# SALIDA_RF.net
KiCad netlist of a schematic drawn in Altium Designer
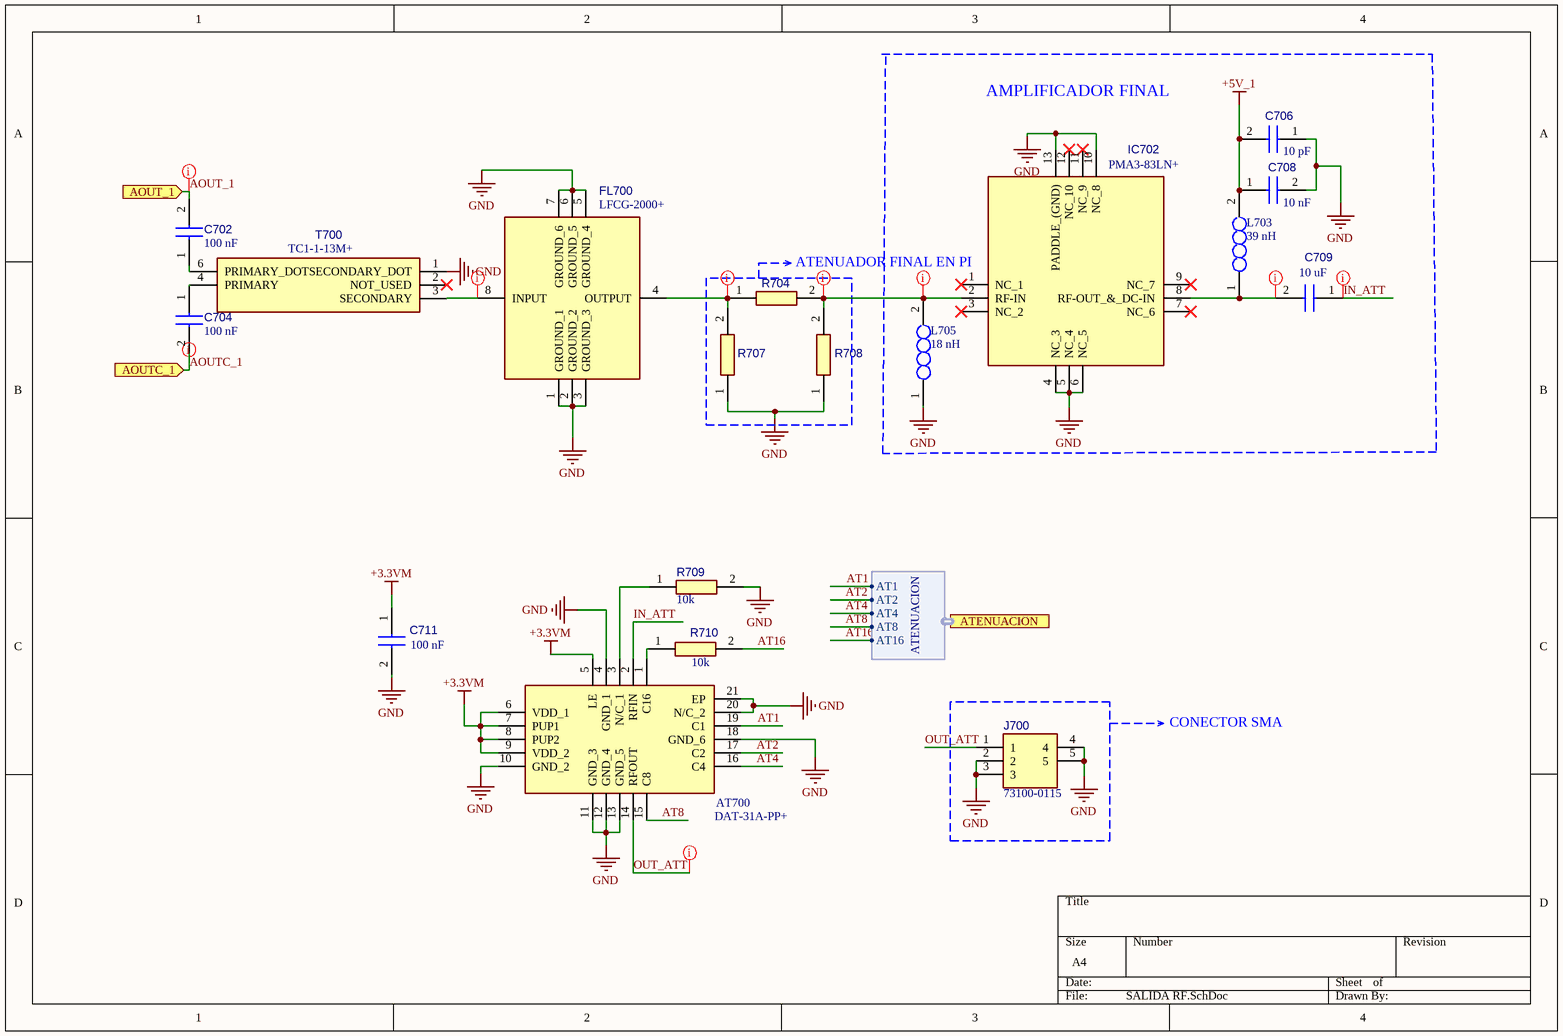
[diagram p0: SALIDA RF.SchDoc]

(export (version "E")
  (design (tool "Eeschema 10.0.6"))
  (components
    (comp (ref "AT700")
      (value "DAT-31A-PP+")
      (footprint "SamacSys:QFN50P400X400X85-21N")
      (description "Attenuator or Isolator")
      (fields (field (name "MOUSER PART NUMBER") "139-DAT-31A-PP+"))
      (libsource (lib "SamacSys") (part "DAT-31A-PP+"))
    )
    (comp (ref "C702")
      (value "100 nF")
      (footprint "SamacSys:C0603")
      (description "Capacitor")
      (fields (field (name "MANUFACTURER_PART_NUMBER") "C0603H470J5GACTU"))
      (libsource (lib "*") (part "C0603H470J5GACTU"))
    )
    (comp (ref "C704")
      (value "100 nF")
      (footprint "SamacSys:C0603")
      (description "Capacitor")
      (fields (field (name "MANUFACTURER_PART_NUMBER") "C0603H470J5GACTU"))
      (libsource (lib "*") (part "C0603H470J5GACTU"))
    )
    (comp (ref "C706")
      (value "10 pF")
      (footprint "SamacSys:C0603")
      (description "Capacitor")
      (fields (field (name "MANUFACTURER_PART_NUMBER") "C0603H470J5GACTU"))
      (libsource (lib "*") (part "C0603H470J5GACTU"))
    )
    (comp (ref "C708")
      (value "10 nF")
      (footprint "SamacSys:C0603")
      (description "Capacitor")
      (fields (field (name "MANUFACTURER_PART_NUMBER") "C0603H470J5GACTU"))
      (libsource (lib "*") (part "C0603H470J5GACTU"))
    )
    (comp (ref "C709")
      (value "10 uF")
      (footprint "SamacSys:C0603")
      (description "Capacitor")
      (fields (field (name "MANUFACTURER_PART_NUMBER") "C0603H470J5GACTU"))
      (libsource (lib "*") (part "C0603H470J5GACTU"))
    )
    (comp (ref "C711")
      (value "100 nF")
      (footprint "SamacSys:C0603")
      (description "Capacitor")
      (fields (field (name "MANUFACTURER_PART_NUMBER") "C0603H470J5GACTU"))
      (libsource (lib "*") (part "C0603H470J5GACTU"))
    )
    (comp (ref "FL700")
      (value "LFCG-2000+")
      (footprint "SamacSys:LFCG2000")
      (description "Filter")
      (fields (field (name "MOUSER PART NUMBER") "139-LFCG-2000+"))
      (libsource (lib "*") (part "LFCG-2000+"))
    )
    (comp (ref "IC702")
      (value "PMA3-83LN+")
      (footprint "SamacSys:QFN51P300X300X89-13N")
      (description "Integrated Circuit")
      (fields (field (name "MOUSER PART NUMBER") "139-PMA3-83LN"))
      (libsource (lib "*") (part "PMA3-83LN+"))
    )
    (comp (ref "J700")
      (value "73100-0115")
      (footprint "SamacSys:731000115")
      (description "Connector")
      (fields (field (name "MOUSER PART NUMBER") "538-73100-0115"))
      (libsource (lib "*") (part "73100-0115"))
    )
    (comp (ref "L703")
      (value "39 nH")
      (footprint "SamacSys:INDC1608X95N")
      (description "Inductor")
      (fields
        (field (name "MANUFACTURER_PART_NUMBER") "AIML-0603-100K-T")
        (field (name "MOUSER PART NUMBER") "815-AIML-0603-100KT")
      )
      (libsource (lib "*") (part "AIML-0603-100K-T"))
    )
    (comp (ref "L705")
      (value "18 nH")
      (footprint "SamacSys:INDC1608X95N")
      (description "Inductor")
      (fields
        (field (name "MANUFACTURER_PART_NUMBER") "AIML-0603-100K-T")
        (field (name "MOUSER PART NUMBER") "815-AIML-0603-100KT")
      )
      (libsource (lib "*") (part "AIML-0603-100K-T"))
    )
    (comp (ref "R704")
      (value "0")
      (footprint "SamacSys:RESC1608X55N")
      (description "Resistor")
      (fields
        (field (name "MANUFACTURER_PART_NUMBER") "CR0603-FX-1431ELF")
        (field (name "MOUSER PART NUMBER") "652-CR0603FX-1431ELF")
      )
      (libsource (lib "*") (part "CR0603-FX-1431ELF"))
    )
    (comp (ref "R707")
      (value "ATENUADOR")
      (footprint "SamacSys:RESC1608X55N")
      (description "Resistor")
      (fields
        (field (name "MANUFACTURER_PART_NUMBER") "CR0603-FX-1431ELF")
        (field (name "MOUSER PART NUMBER") "652-CR0603FX-1431ELF")
      )
      (libsource (lib "") (part "CR0603-FX-1431ELF_1"))
    )
    (comp (ref "R708")
      (value "ATENUADOR")
      (footprint "SamacSys:RESC1608X55N")
      (description "Resistor")
      (fields
        (field (name "MANUFACTURER_PART_NUMBER") "CR0603-FX-1431ELF")
        (field (name "MOUSER PART NUMBER") "652-CR0603FX-1431ELF")
      )
      (libsource (lib "") (part "CR0603-FX-1431ELF_1"))
    )
    (comp (ref "R709")
      (value "10k")
      (footprint "SamacSys:RESC1608X55N")
      (description "Resistor")
      (fields
        (field (name "MANUFACTURER_PART_NUMBER") "CR0603-FX-1431ELF")
        (field (name "MOUSER PART NUMBER") "652-CR0603FX-1431ELF")
      )
      (libsource (lib "*") (part "CR0603-FX-1431ELF"))
    )
    (comp (ref "R710")
      (value "10k")
      (footprint "SamacSys:RESC1608X55N")
      (description "Resistor")
      (fields
        (field (name "MANUFACTURER_PART_NUMBER") "CR0603-FX-1431ELF")
        (field (name "MOUSER PART NUMBER") "652-CR0603FX-1431ELF")
      )
      (libsource (lib "*") (part "CR0603-FX-1431ELF"))
    )
    (comp (ref "T700")
      (value "TC1-1-13M+")
      (footprint "SamacSys:TC414")
      (description "Transformer")
      (fields (field (name "MOUSER PART NUMBER") "139-TC1-1-13M"))
      (libsource (lib "*") (part "TC1-1-13M+"))
    )
  )
  (nets
    (net (code "2") (name "+3.3VM") (class "Default")
      (node (ref "AT700") (pin "5") (pinfunction "LE_5") (pintype "passive"))
      (node (ref "AT700") (pin "6") (pinfunction "VDD_1_6") (pintype "passive"))
      (node (ref "AT700") (pin "7") (pinfunction "PUP1_7") (pintype "passive"))
      (node (ref "AT700") (pin "8") (pinfunction "PUP2_8") (pintype "passive"))
      (node (ref "AT700") (pin "9") (pinfunction "VDD_2_9") (pintype "passive"))
      (node (ref "C711") (pin "1") (pinfunction "1_1") (pintype "passive"))
    )
    (net (code "3") (name "+5V_1") (class "Default")
      (node (ref "C706") (pin "2") (pinfunction "2_2") (pintype "passive"))
      (node (ref "C708") (pin "1") (pinfunction "1_1") (pintype "passive"))
      (node (ref "L703") (pin "2") (pinfunction "2_2") (pintype "passive"))
    )
    (net (code "4") (name "/AOUTC_1") (class "Default")
      (node (ref "C704") (pin "2") (pinfunction "2_2") (pintype "passive"))
    )
    (net (code "5") (name "/AOUT_1") (class "Default")
      (node (ref "C702") (pin "2") (pinfunction "2_2") (pintype "passive"))
    )
    (net (code "6") (name "/AT1") (class "Default")
      (node (ref "AT700") (pin "19") (pinfunction "C1_19") (pintype "passive"))
    )
    (net (code "7") (name "/AT2") (class "Default")
      (node (ref "AT700") (pin "17") (pinfunction "C2_17") (pintype "passive"))
    )
    (net (code "8") (name "/AT4") (class "Default")
      (node (ref "AT700") (pin "16") (pinfunction "C4_16") (pintype "passive"))
    )
    (net (code "9") (name "/AT8") (class "Default")
      (node (ref "AT700") (pin "15") (pinfunction "C8_15") (pintype "passive"))
    )
    (net (code "10") (name "/AT16") (class "Default")
      (node (ref "R710") (pin "2") (pinfunction "2_2") (pintype "passive"))
    )
    (net (code "11") (name "/IN_ATT") (class "Default")
      (node (ref "AT700") (pin "2") (pinfunction "RFIN_2") (pintype "passive"))
      (node (ref "C709") (pin "1") (pinfunction "1_1") (pintype "passive"))
    )
    (net (code "12") (name "/OUT_ATT") (class "Default")
      (node (ref "AT700") (pin "14") (pinfunction "RFOUT_14") (pintype "passive"))
      (node (ref "J700") (pin "1") (pinfunction "1_1") (pintype "passive"))
    )
    (net (code "14") (name "GND") (class "Default")
      (node (ref "AT700") (pin "10") (pinfunction "GND_2_10") (pintype "passive"))
      (node (ref "AT700") (pin "11") (pinfunction "GND_3_11") (pintype "passive"))
      (node (ref "AT700") (pin "12") (pinfunction "GND_4_12") (pintype "passive"))
      (node (ref "AT700") (pin "13") (pinfunction "GND_5_13") (pintype "passive"))
      (node (ref "AT700") (pin "18") (pinfunction "GND_6_18") (pintype "passive"))
      (node (ref "AT700") (pin "20") (pinfunction "N/C_2_20") (pintype "passive"))
      (node (ref "AT700") (pin "21") (pinfunction "EP_21") (pintype "passive"))
      (node (ref "AT700") (pin "4") (pinfunction "GND_1_4") (pintype "passive"))
      (node (ref "C706") (pin "1") (pinfunction "1_1") (pintype "passive"))
      (node (ref "C708") (pin "2") (pinfunction "2_2") (pintype "passive"))
      (node (ref "C711") (pin "2") (pinfunction "2_2") (pintype "passive"))
      (node (ref "FL700") (pin "1") (pinfunction "GROUND_1_1") (pintype "passive"))
      (node (ref "FL700") (pin "2") (pinfunction "GROUND_2_2") (pintype "passive"))
      (node (ref "FL700") (pin "3") (pinfunction "GROUND_3_3") (pintype "passive"))
      (node (ref "FL700") (pin "5") (pinfunction "GROUND_4_5") (pintype "passive"))
      (node (ref "FL700") (pin "6") (pinfunction "GROUND_5_6") (pintype "passive"))
      (node (ref "FL700") (pin "7") (pinfunction "GROUND_6_7") (pintype "passive"))
      (node (ref "IC702") (pin "10") (pinfunction "NC_8_10") (pintype "passive"))
      (node (ref "IC702") (pin "13") (pinfunction "PADDLE_(GND)_13") (pintype "passive"))
      (node (ref "IC702") (pin "4") (pinfunction "NC_3_4") (pintype "passive"))
      (node (ref "IC702") (pin "5") (pinfunction "NC_4_5") (pintype "passive"))
      (node (ref "IC702") (pin "6") (pinfunction "NC_5_6") (pintype "passive"))
      (node (ref "J700") (pin "2") (pinfunction "2_2") (pintype "passive"))
      (node (ref "J700") (pin "3") (pinfunction "3_3") (pintype "passive"))
      (node (ref "J700") (pin "4") (pinfunction "4_4") (pintype "passive"))
      (node (ref "J700") (pin "5") (pinfunction "5_5") (pintype "passive"))
      (node (ref "L705") (pin "1") (pinfunction "1_1") (pintype "passive"))
      (node (ref "R707") (pin "1") (pinfunction "1_1") (pintype "passive"))
      (node (ref "R708") (pin "1") (pinfunction "1_1") (pintype "passive"))
      (node (ref "R709") (pin "2") (pinfunction "2_2") (pintype "passive"))
      (node (ref "T700") (pin "1") (pinfunction "SECONDARY_DOT_1") (pintype "passive"))
    )
    (net (code "15") (name "Net-(AT700-C16)") (class "Default")
      (node (ref "AT700") (pin "1") (pinfunction "C16_1") (pintype "passive"))
      (node (ref "R710") (pin "1") (pinfunction "1_1") (pintype "passive"))
    )
    (net (code "16") (name "Net-(AT700-N{slash}C_1)") (class "Default")
      (node (ref "AT700") (pin "3") (pinfunction "N/C_1_3") (pintype "passive"))
      (node (ref "R709") (pin "1") (pinfunction "1_1") (pintype "passive"))
    )
    (net (code "17") (name "Net-(FL700-INPUT)") (class "Default")
      (node (ref "FL700") (pin "8") (pinfunction "INPUT_8") (pintype "passive"))
      (node (ref "T700") (pin "3") (pinfunction "SECONDARY_3") (pintype "passive"))
    )
    (net (code "18") (name "Net-(FL700-OUTPUT)") (class "Default")
      (node (ref "FL700") (pin "4") (pinfunction "OUTPUT_4") (pintype "passive"))
      (node (ref "R704") (pin "1") (pinfunction "1_1") (pintype "passive"))
      (node (ref "R707") (pin "2") (pinfunction "2_2") (pintype "passive"))
    )
    (net (code "19") (name "Net-(IC702-RF-IN)") (class "Default")
      (node (ref "IC702") (pin "2") (pinfunction "RF-IN_2") (pintype "passive"))
      (node (ref "L705") (pin "2") (pinfunction "2_2") (pintype "passive"))
      (node (ref "R704") (pin "2") (pinfunction "2_2") (pintype "passive"))
      (node (ref "R708") (pin "2") (pinfunction "2_2") (pintype "passive"))
    )
    (net (code "20") (name "Net-(IC702-RF-OUT_&_DC-IN)") (class "Default")
      (node (ref "C709") (pin "2") (pinfunction "2_2") (pintype "passive"))
      (node (ref "IC702") (pin "8") (pinfunction "RF-OUT_&_DC-IN_8") (pintype "passive"))
      (node (ref "L703") (pin "1") (pinfunction "1_1") (pintype "passive"))
    )
    (net (code "21") (name "Net-(T700-PRIMARY)") (class "Default")
      (node (ref "C704") (pin "1") (pinfunction "1_1") (pintype "passive"))
      (node (ref "T700") (pin "4") (pinfunction "PRIMARY_4") (pintype "passive"))
    )
    (net (code "22") (name "Net-(T700-PRIMARY_DOT)") (class "Default")
      (node (ref "C702") (pin "1") (pinfunction "1_1") (pintype "passive"))
      (node (ref "T700") (pin "6") (pinfunction "PRIMARY_DOT_6") (pintype "passive"))
    )
    (net (code "23") (name "unconnected-(IC702-NC_1-Pad1)") (class "Default")
      (node (ref "IC702") (pin "1") (pinfunction "NC_1_1") (pintype "passive+no_connect"))
    )
    (net (code "24") (name "unconnected-(IC702-NC_2-Pad3)") (class "Default")
      (node (ref "IC702") (pin "3") (pinfunction "NC_2_3") (pintype "passive+no_connect"))
    )
    (net (code "25") (name "unconnected-(IC702-NC_6-Pad7)") (class "Default")
      (node (ref "IC702") (pin "7") (pinfunction "NC_6_7") (pintype "passive+no_connect"))
    )
    (net (code "26") (name "unconnected-(IC702-NC_7-Pad9)") (class "Default")
      (node (ref "IC702") (pin "9") (pinfunction "NC_7_9") (pintype "passive+no_connect"))
    )
    (net (code "27") (name "unconnected-(IC702-NC_9-Pad11)") (class "Default")
      (node (ref "IC702") (pin "11") (pinfunction "NC_9_11") (pintype "passive+no_connect"))
    )
    (net (code "28") (name "unconnected-(IC702-NC_10-Pad12)") (class "Default")
      (node (ref "IC702") (pin "12") (pinfunction "NC_10_12") (pintype "passive+no_connect"))
    )
    (net (code "29") (name "unconnected-(T700-NOT_USED-Pad2)") (class "Default")
      (node (ref "T700") (pin "2") (pinfunction "NOT_USED_2") (pintype "passive+no_connect"))
    )
  )
)
